# fl3xwatch.net
KiCad netlist of a schematic drawn in EAGLE
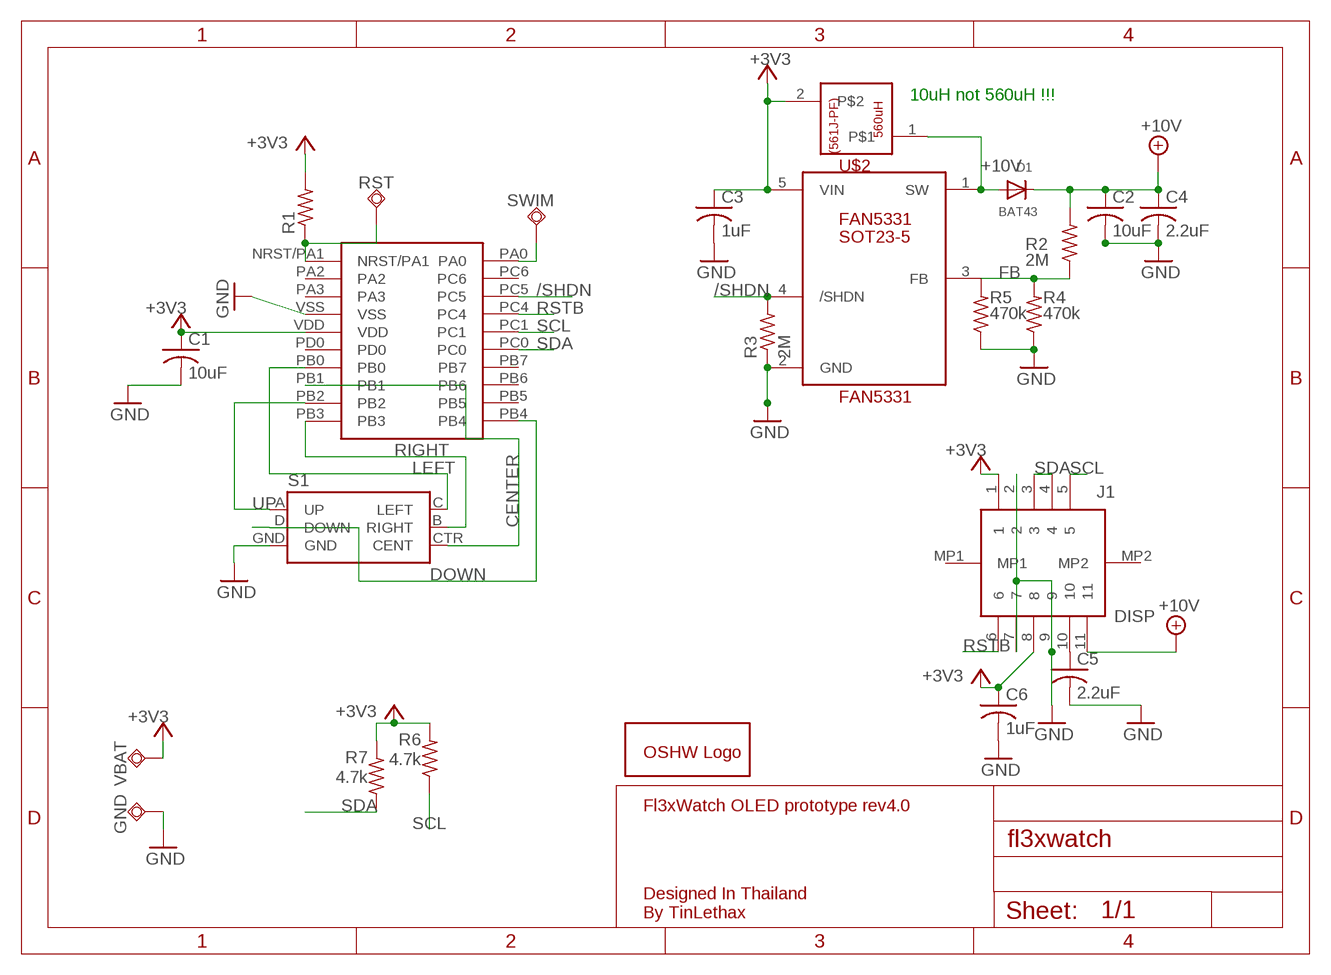
[diagram p0: schematic, sheet 1]

(export (version "E")
  (design (tool "Eeschema 10.0.6"))
  (components
    (comp (ref "C1")
      (value "10uF")
      (footprint "eagle-import:C0805")
      (libsource (lib "eagle-import") (part "C-USC0805"))
    )
    (comp (ref "C2")
      (value "10uF")
      (footprint "eagle-import:C0805")
      (libsource (lib "eagle-import") (part "C-USC0805"))
    )
    (comp (ref "C3")
      (value "1uF")
      (footprint "eagle-import:C0603")
      (libsource (lib "eagle-import") (part "C-USC0603"))
    )
    (comp (ref "C4")
      (value "2.2uF")
      (footprint "eagle-import:C0603")
      (libsource (lib "eagle-import") (part "C-USC0603"))
    )
    (comp (ref "C5")
      (value "2.2uF")
      (footprint "eagle-import:C0603")
      (libsource (lib "eagle-import") (part "C-USC0603"))
    )
    (comp (ref "C6")
      (value "1uF")
      (footprint "eagle-import:C0603")
      (libsource (lib "eagle-import") (part "C-USC0603"))
    )
    (comp (ref "D1")
      (value "BAT43")
      (footprint "eagle-import:SOD-323F")
      (libsource (lib "eagle-import") (part "DIODESOD-323F"))
    )
    (comp (ref "GND")
      (value "TPSQTP20SQ")
      (footprint "eagle-import:TP20SQ")
      (libsource (lib "eagle-import") (part "TPSQTP20SQ"))
    )
    (comp (ref "GOLD_ORB_SM1")
      (value "OSHWLOGOLOGO5MM")
      (footprint "eagle-import:OSHW_5MM")
      (libsource (lib "eagle-import") (part "OSHWLOGOLOGO5MM"))
    )
    (comp (ref "J1")
      (value "DISP")
      (footprint "eagle-import:FH35C11S03SHW50")
      (fields
        (field (name "MANUFACTURER_PART_NUMBER") "FH35C-11S-0.3SHW(50)")
        (field (name "MOUSER_PART_NUMBER") "798-FH35C11S03SHW50")
      )
      (libsource (lib "eagle-import") (part "FH35C-11S-0.3SHW_50_"))
    )
    (comp (ref "L1")
      (value "10uH")
      (footprint "eagle-import:INDC4526X50N")
      (libsource (lib "eagle-import") (part "NL453232T-561J-PF"))
    )
    (comp (ref "R1")
      (value "R-US_R0603")
      (footprint "eagle-import:R0603")
      (libsource (lib "eagle-import") (part "R-US_R0603"))
    )
    (comp (ref "R2")
      (value "2M")
      (footprint "eagle-import:R0603")
      (libsource (lib "eagle-import") (part "R-US_R0603"))
    )
    (comp (ref "R3")
      (value "2M")
      (footprint "eagle-import:R0603")
      (libsource (lib "eagle-import") (part "R-US_R0603"))
    )
    (comp (ref "R4")
      (value "470k")
      (footprint "eagle-import:R0805")
      (libsource (lib "eagle-import") (part "R-US_R0805"))
    )
    (comp (ref "R5")
      (value "470k")
      (footprint "eagle-import:R0805")
      (libsource (lib "eagle-import") (part "R-US_R0805"))
    )
    (comp (ref "R6")
      (value "4.7k")
      (footprint "eagle-import:R0603")
      (libsource (lib "eagle-import") (part "R-US_R0603"))
    )
    (comp (ref "R7")
      (value "4.7k")
      (footprint "eagle-import:R0603")
      (libsource (lib "eagle-import") (part "R-US_R0603"))
    )
    (comp (ref "RST")
      (value "TPSQTP15R")
      (footprint "eagle-import:TP15R")
      (libsource (lib "eagle-import") (part "TPSQTP15R"))
    )
    (comp (ref "S1")
      (value "SPARKFUN-ELECTROMECHANICAL_JOYSTICK_MINI")
      (footprint "eagle-import:SPARKFUN-ELECTROMECHANICAL_JOYSTICK_MINI")
      (libsource (lib "eagle-import") (part "SPARKFUN-ELECTROMECHANICAL_JOYSTICK_MINI"))
    )
    (comp (ref "SWIM")
      (value "TPSQTP15R")
      (footprint "eagle-import:TP15R")
      (libsource (lib "eagle-import") (part "TPSQTP15R"))
    )
    (comp (ref "U$1")
      (value "STM8L151F3")
      (footprint "eagle-import:UFQFPN-20")
      (libsource (lib "eagle-import") (part "STM8L151F3"))
    )
    (comp (ref "U$2")
      (value "FAN5331")
      (footprint "eagle-import:SOT95P280X145-5N")
      (libsource (lib "eagle-import") (part "FAN5331"))
    )
    (comp (ref "VBAT")
      (value "TPSQTP20SQ")
      (footprint "eagle-import:TP20SQ")
      (libsource (lib "eagle-import") (part "TPSQTP20SQ"))
    )
  )
  (nets
    (net (code "1") (name "+3V3") (class "Default")
      (node (ref "C1") (pin "1") (pinfunction "1_1") (pintype "passive"))
      (node (ref "C3") (pin "1") (pinfunction "1_1") (pintype "passive"))
      (node (ref "C6") (pin "1") (pinfunction "1_1") (pintype "passive"))
      (node (ref "J1") (pin "1") (pinfunction "1_1") (pintype "bidirectional"))
      (node (ref "J1") (pin "8") (pinfunction "8_8") (pintype "bidirectional"))
      (node (ref "L1") (pin "2") (pinfunction "P$2_2") (pintype "bidirectional"))
      (node (ref "R1") (pin "2") (pinfunction "2_2") (pintype "passive"))
      (node (ref "R6") (pin "2") (pinfunction "2_2") (pintype "passive"))
      (node (ref "R7") (pin "2") (pinfunction "2_2") (pintype "passive"))
      (node (ref "U$1") (pin "VDD") (pinfunction "VDD_VDD") (pintype "bidirectional"))
      (node (ref "U$2") (pin "5") (pinfunction "VIN_5") (pintype "bidirectional"))
      (node (ref "VBAT") (pin "TP") (pinfunction "TP_TP") (pintype "input"))
    )
    (net (code "2") (name "+10V") (class "Default")
      (node (ref "C2") (pin "1") (pinfunction "1_1") (pintype "passive"))
      (node (ref "C4") (pin "1") (pinfunction "1_1") (pintype "passive"))
      (node (ref "D1") (pin "C") (pinfunction "C_C") (pintype "passive"))
      (node (ref "J1") (pin "11") (pinfunction "11_11") (pintype "bidirectional"))
      (node (ref "R2") (pin "2") (pinfunction "2_2") (pintype "passive"))
    )
    (net (code "3") (name "/CENTER") (class "Default")
      (node (ref "S1") (pin "CTR") (pinfunction "CENT_CTR") (pintype "bidirectional"))
      (node (ref "U$1") (pin "PB1") (pinfunction "PB1_PB1") (pintype "bidirectional"))
    )
    (net (code "4") (name "/DOWN") (class "Default")
      (node (ref "S1") (pin "D") (pinfunction "DOWN_D") (pintype "bidirectional"))
      (node (ref "U$1") (pin "PB4") (pinfunction "PB4_PB4") (pintype "bidirectional"))
    )
    (net (code "5") (name "/FB") (class "Default")
      (node (ref "R2") (pin "1") (pinfunction "1_1") (pintype "passive"))
      (node (ref "R4") (pin "2") (pinfunction "2_2") (pintype "passive"))
      (node (ref "R5") (pin "2") (pinfunction "2_2") (pintype "passive"))
      (node (ref "U$2") (pin "3") (pinfunction "FB_3") (pintype "bidirectional"))
    )
    (net (code "6") (name "/LEFT") (class "Default")
      (node (ref "S1") (pin "C") (pinfunction "LEFT_C") (pintype "bidirectional"))
      (node (ref "U$1") (pin "PB0") (pinfunction "PB0_PB0") (pintype "bidirectional"))
    )
    (net (code "7") (name "/RIGHT") (class "Default")
      (node (ref "S1") (pin "B") (pinfunction "RIGHT_B") (pintype "bidirectional"))
      (node (ref "U$1") (pin "PB3") (pinfunction "PB3_PB3") (pintype "bidirectional"))
    )
    (net (code "8") (name "/RSTB") (class "Default")
      (node (ref "J1") (pin "6") (pinfunction "6_6") (pintype "bidirectional"))
      (node (ref "U$1") (pin "PC4") (pinfunction "PC4_PC4") (pintype "bidirectional"))
    )
    (net (code "9") (name "/SCL") (class "Default")
      (node (ref "J1") (pin "5") (pinfunction "5_5") (pintype "bidirectional"))
      (node (ref "R6") (pin "1") (pinfunction "1_1") (pintype "passive"))
      (node (ref "U$1") (pin "PC1") (pinfunction "PC1_PC1") (pintype "bidirectional"))
    )
    (net (code "10") (name "/SDA") (class "Default")
      (node (ref "J1") (pin "3") (pinfunction "3_3") (pintype "bidirectional"))
      (node (ref "J1") (pin "4") (pinfunction "4_4") (pintype "bidirectional"))
      (node (ref "R7") (pin "1") (pinfunction "1_1") (pintype "passive"))
      (node (ref "U$1") (pin "PC0") (pinfunction "PC0_PC0") (pintype "bidirectional"))
    )
    (net (code "11") (name "/UP") (class "Default")
      (node (ref "S1") (pin "A") (pinfunction "UP_A") (pintype "bidirectional"))
      (node (ref "U$1") (pin "PB2") (pinfunction "PB2_PB2") (pintype "bidirectional"))
    )
    (net (code "12") (name "/{slash}SHDN") (class "Default")
      (node (ref "R3") (pin "2") (pinfunction "2_2") (pintype "passive"))
      (node (ref "U$1") (pin "PC5") (pinfunction "PC5_PC5") (pintype "bidirectional"))
      (node (ref "U$2") (pin "4") (pinfunction "/SHDN_4") (pintype "bidirectional"))
    )
    (net (code "13") (name "GND") (class "Default")
      (node (ref "C1") (pin "2") (pinfunction "2_2") (pintype "passive"))
      (node (ref "C2") (pin "2") (pinfunction "2_2") (pintype "passive"))
      (node (ref "C3") (pin "2") (pinfunction "2_2") (pintype "passive"))
      (node (ref "C4") (pin "2") (pinfunction "2_2") (pintype "passive"))
      (node (ref "C5") (pin "2") (pinfunction "2_2") (pintype "passive"))
      (node (ref "C6") (pin "2") (pinfunction "2_2") (pintype "passive"))
      (node (ref "GND") (pin "TP") (pinfunction "TP_TP") (pintype "input"))
      (node (ref "J1") (pin "2") (pinfunction "2_2") (pintype "bidirectional"))
      (node (ref "J1") (pin "7") (pinfunction "7_7") (pintype "bidirectional"))
      (node (ref "J1") (pin "9") (pinfunction "9_9") (pintype "bidirectional"))
      (node (ref "R3") (pin "1") (pinfunction "1_1") (pintype "passive"))
      (node (ref "R4") (pin "1") (pinfunction "1_1") (pintype "passive"))
      (node (ref "R5") (pin "1") (pinfunction "1_1") (pintype "passive"))
      (node (ref "S1") (pin "GND") (pinfunction "GND_GND") (pintype "bidirectional"))
      (node (ref "U$1") (pin "VSS") (pinfunction "VSS_VSS") (pintype "bidirectional"))
      (node (ref "U$2") (pin "2") (pinfunction "GND_2") (pintype "bidirectional"))
    )
    (net (code "14") (name "Net-(C5-Pad1)") (class "Default")
      (node (ref "C5") (pin "1") (pinfunction "1_1") (pintype "passive"))
      (node (ref "J1") (pin "10") (pinfunction "10_10") (pintype "bidirectional"))
    )
    (net (code "15") (name "Net-(L1-P$1)") (class "Default")
      (node (ref "D1") (pin "A") (pinfunction "A_A") (pintype "passive"))
      (node (ref "L1") (pin "1") (pinfunction "P$1_1") (pintype "bidirectional"))
      (node (ref "U$2") (pin "1") (pinfunction "SW_1") (pintype "bidirectional"))
    )
    (net (code "16") (name "Net-(R1-Pad1)") (class "Default")
      (node (ref "R1") (pin "1") (pinfunction "1_1") (pintype "passive"))
      (node (ref "RST") (pin "TP") (pinfunction "TP_TP") (pintype "input"))
      (node (ref "U$1") (pin "NRST/PA1") (pinfunction "NRST/PA1_NRST/PA1") (pintype "bidirectional"))
    )
    (net (code "17") (name "Net-(SWIM-PadTP)") (class "Default")
      (node (ref "SWIM") (pin "TP") (pinfunction "TP_TP") (pintype "input"))
      (node (ref "U$1") (pin "PA0") (pinfunction "PA0_PA0") (pintype "bidirectional"))
    )
    (net (code "18") (name "unconnected-(J1-PadMP1)") (class "Default")
      (node (ref "J1") (pin "MP1") (pinfunction "MP1_MP1") (pintype "bidirectional"))
    )
    (net (code "19") (name "unconnected-(J1-PadMP2)") (class "Default")
      (node (ref "J1") (pin "MP2") (pinfunction "MP2_MP2") (pintype "bidirectional"))
    )
    (net (code "20") (name "unconnected-(U$1-PadPA2)") (class "Default")
      (node (ref "U$1") (pin "PA2") (pinfunction "PA2_PA2") (pintype "bidirectional"))
    )
    (net (code "21") (name "unconnected-(U$1-PadPA3)") (class "Default")
      (node (ref "U$1") (pin "PA3") (pinfunction "PA3_PA3") (pintype "bidirectional"))
    )
    (net (code "22") (name "unconnected-(U$1-PadPB5)") (class "Default")
      (node (ref "U$1") (pin "PB5") (pinfunction "PB5_PB5") (pintype "bidirectional"))
    )
    (net (code "23") (name "unconnected-(U$1-PadPB6)") (class "Default")
      (node (ref "U$1") (pin "PB6") (pinfunction "PB6_PB6") (pintype "bidirectional"))
    )
    (net (code "24") (name "unconnected-(U$1-PadPB7)") (class "Default")
      (node (ref "U$1") (pin "PB7") (pinfunction "PB7_PB7") (pintype "bidirectional"))
    )
    (net (code "25") (name "unconnected-(U$1-PadPC6)") (class "Default")
      (node (ref "U$1") (pin "PC6") (pinfunction "PC6_PC6") (pintype "bidirectional"))
    )
    (net (code "26") (name "unconnected-(U$1-PadPD0)") (class "Default")
      (node (ref "U$1") (pin "PD0") (pinfunction "PD0_PD0") (pintype "bidirectional"))
    )
  )
)
